# 08_ETHERNET.net
KiCad netlist of a schematic drawn in Altium Designer
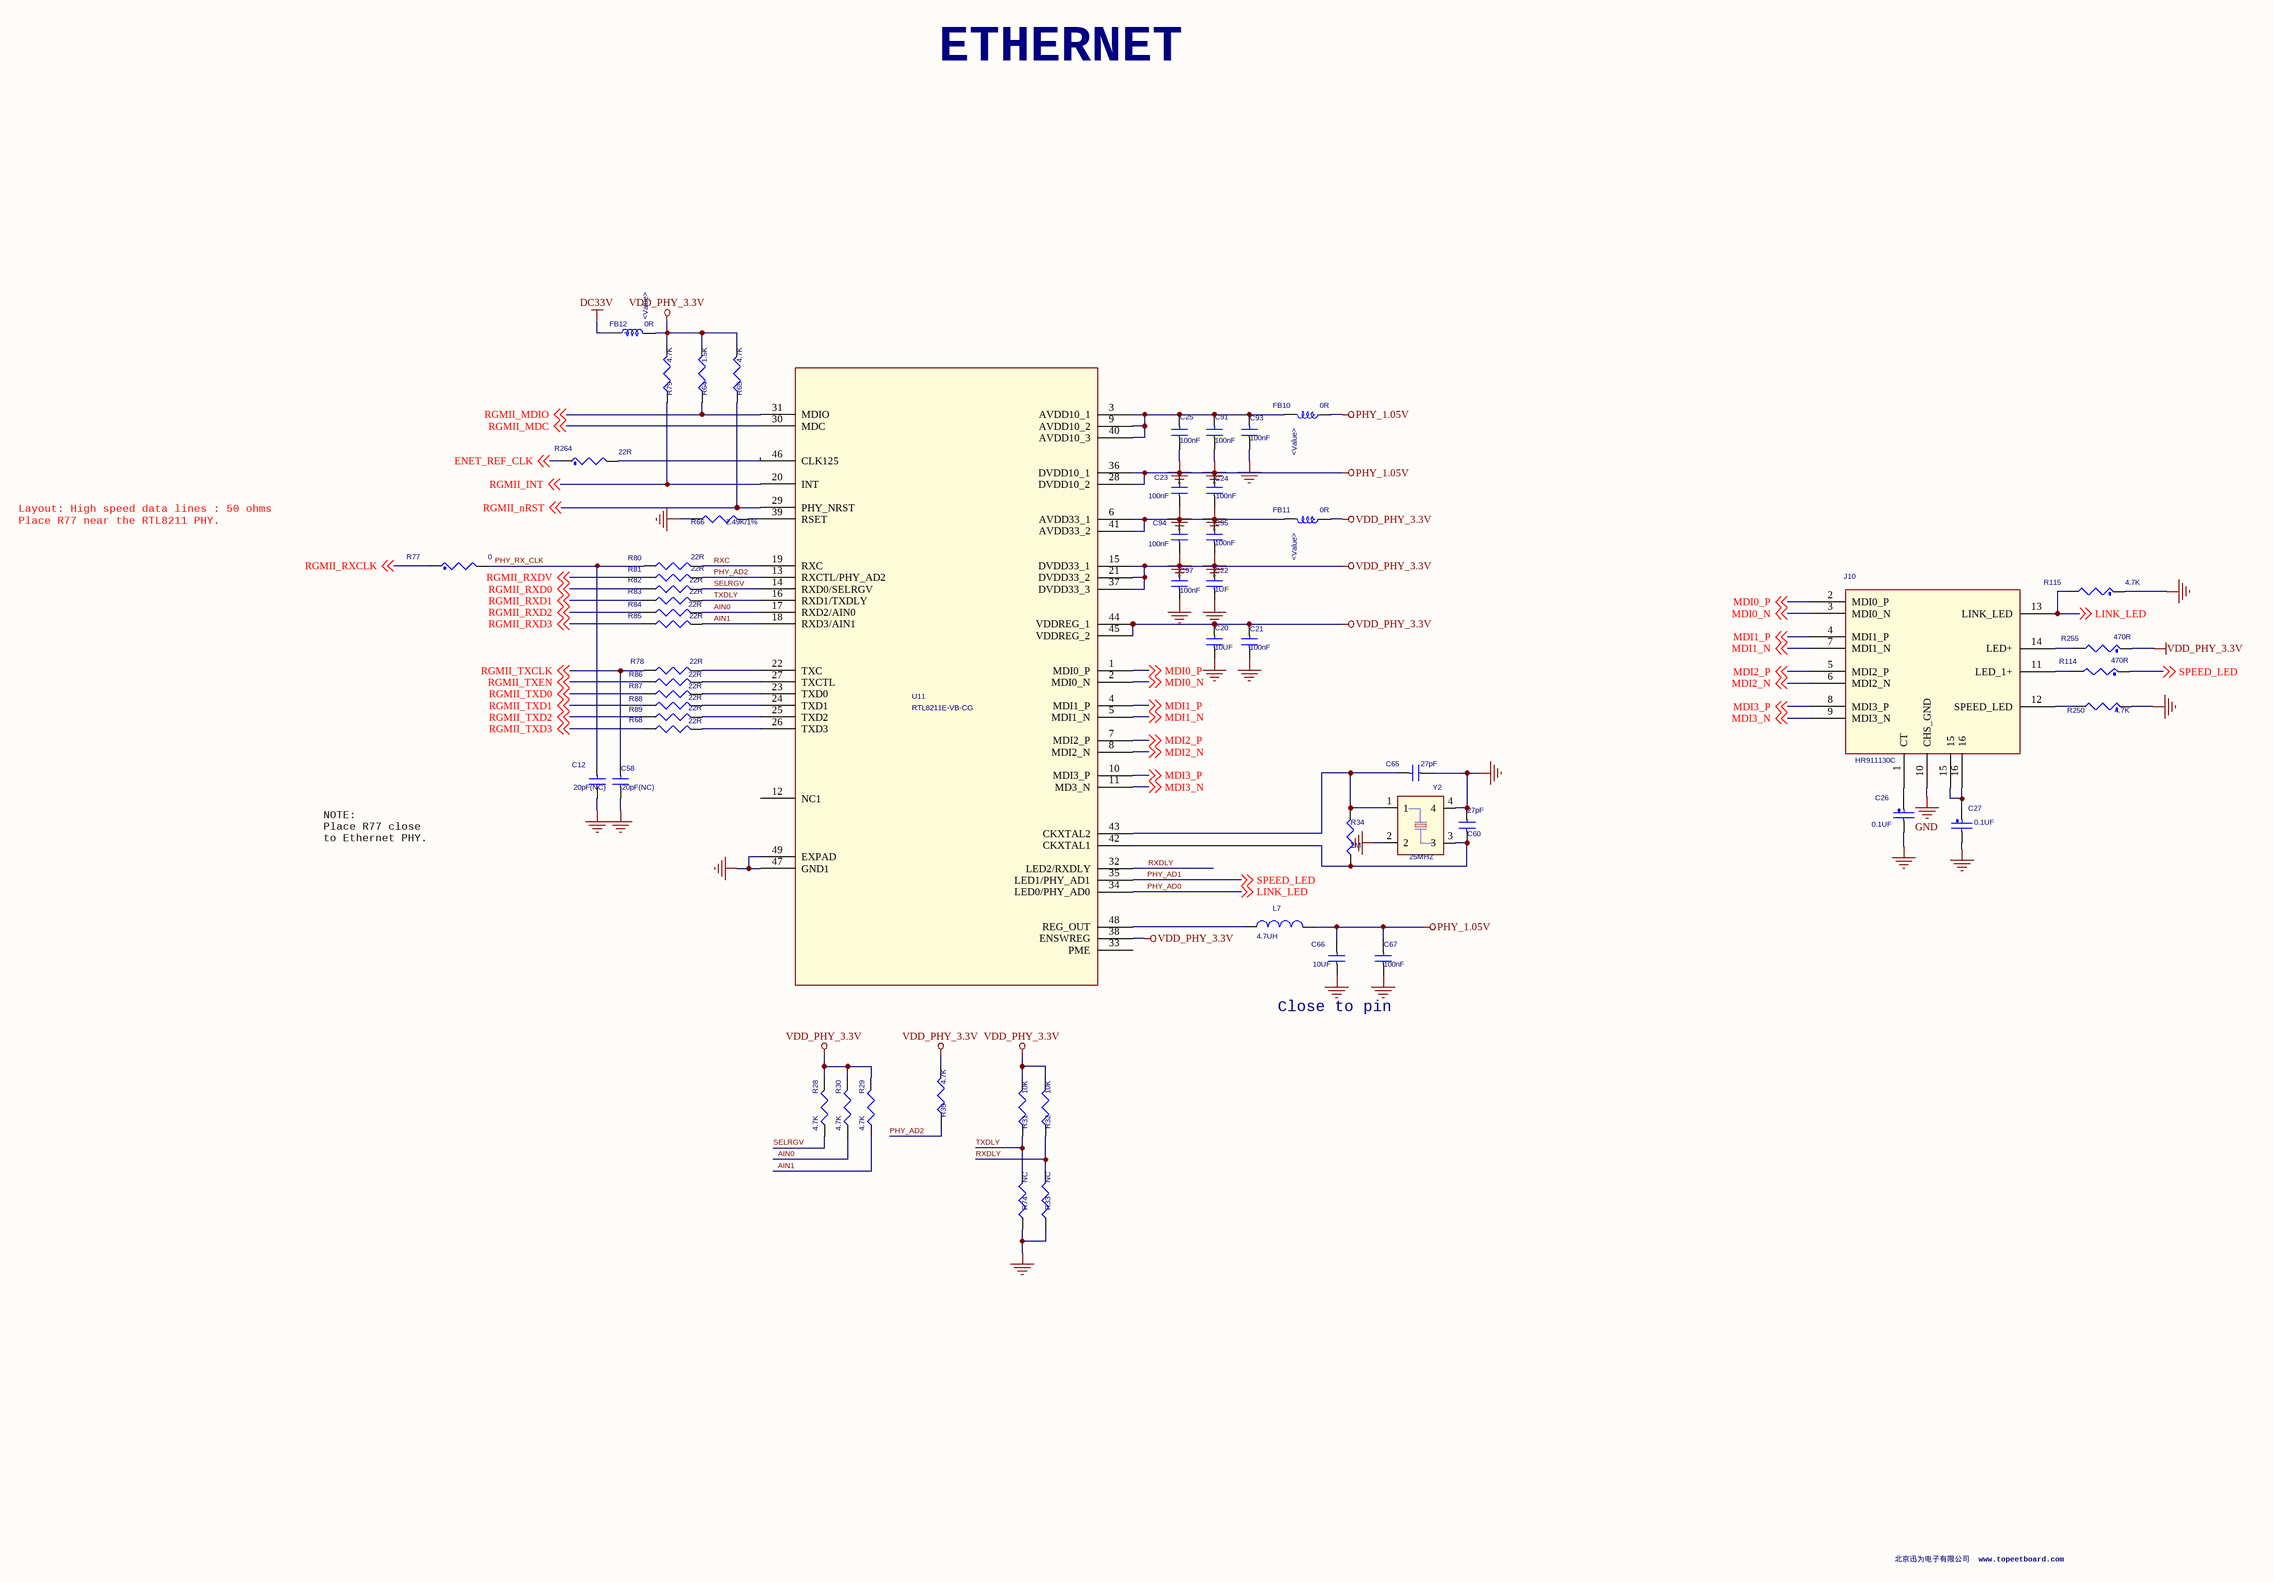
[diagram p0: 08 ETHERNET.SchDoc]

(export (version "E")
  (design (tool "Eeschema 10.0.6"))
  (components
    (comp (ref "C12") (value "20pF(NC)") (libsource (lib "*") (part "CAP")))
    (comp (ref "C20") (value "10UF") (libsource (lib "*") (part "CAP")))
    (comp (ref "C21") (value "100nF") (libsource (lib "*") (part "CAP")))
    (comp (ref "C22") (value "1UF") (libsource (lib "*") (part "CAP")))
    (comp (ref "C23") (value "100nF") (libsource (lib "*") (part "CAP")))
    (comp (ref "C24") (value "100nF") (libsource (lib "*") (part "CAP")))
    (comp (ref "C25") (value "100nF") (libsource (lib "*") (part "CAP")))
    (comp (ref "C26")
      (value "0.1UF")
      (description "CAP CER 0.1UF 16V 10% X7R 0402")
      (fields (field (name "TOLERANCE") "10%") (field (name "VOLTAGE") "16V"))
      (libsource (lib "*") (part "CAP_NP"))
    )
    (comp (ref "C27")
      (value "0.1UF")
      (description "CAP CER 0.1UF 16V 10% X7R 0402")
      (fields (field (name "VOLTAGE") "16V") (field (name "TOLERANCE") "10%"))
      (libsource (lib "*") (part "CAP_NP"))
    )
    (comp (ref "C58") (value "20pF(NC)") (libsource (lib "*") (part "CAP")))
    (comp (ref "C60") (value "27pF") (libsource (lib "*") (part "CAP")))
    (comp (ref "C65") (value "27pF") (libsource (lib "*") (part "CAP")))
    (comp (ref "C66") (value "10UF") (libsource (lib "*") (part "CAP")))
    (comp (ref "C67") (value "100nF") (libsource (lib "*") (part "CAP")))
    (comp (ref "C91") (value "100nF") (libsource (lib "*") (part "CAP")))
    (comp (ref "C93") (value "100nF") (libsource (lib "*") (part "CAP")))
    (comp (ref "C94") (value "100nF") (libsource (lib "*") (part "CAP")))
    (comp (ref "C95") (value "100nF") (libsource (lib "*") (part "CAP")))
    (comp (ref "C97") (value "100nF") (libsource (lib "*") (part "CAP")))
    (comp (ref "FB10")
      (value "0R")
      (footprint "L0603")
      (description "Inductor,0402，10ohm@100M,")
      (fields
        (field (name "5TH PART FIELD") "<Value>")
        (field (name "MANUFACTURER PART NUMBER") "BLM15AG100SN1")
        (field (name "MANUFACTURER") "Murata")
      )
      (libsource (lib "*") (part "IND_EMI"))
    )
    (comp (ref "FB11")
      (value "0R")
      (footprint "L0603")
      (description "Inductor,0402，10ohm@100M,")
      (fields
        (field (name "5TH PART FIELD") "<Value>")
        (field (name "MANUFACTURER PART NUMBER") "BLM15AG100SN1")
        (field (name "MANUFACTURER") "Murata")
      )
      (libsource (lib "*") (part "IND_EMI"))
    )
    (comp (ref "FB12")
      (value "0R")
      (footprint "L0603")
      (description "Inductor,0402，10ohm@100M,")
      (fields
        (field (name "5TH PART FIELD") "<Value>")
        (field (name "MANUFACTURER PART NUMBER") "BLM15AG100SN1")
        (field (name "MANUFACTURER") "Murata")
      )
      (libsource (lib "*") (part "IND_EMI"))
    )
    (comp (ref "J10") (value "HR911130C") (libsource (lib "*") (part "HR911130C_0")))
    (comp (ref "L7") (value "4.7UH") (libsource (lib "*") (part "INDUCTOR")))
    (comp (ref "R28") (value "4.7K") (libsource (lib "*") (part "RES")))
    (comp (ref "R29") (value "4.7K") (libsource (lib "*") (part "RES")))
    (comp (ref "R30") (value "4.7K") (libsource (lib "*") (part "RES")))
    (comp (ref "R31") (value "10K") (libsource (lib "*") (part "RES")))
    (comp (ref "R32") (value "10K") (libsource (lib "*") (part "RES")))
    (comp (ref "R33") (value "NC") (libsource (lib "*") (part "RES")))
    (comp (ref "R34") (value "1M") (libsource (lib "*") (part "RES")))
    (comp (ref "R35") (value "4.7K") (libsource (lib "*") (part "RES")))
    (comp (ref "R64") (value "1.5K") (libsource (lib "*") (part "RES")))
    (comp (ref "R65") (value "4.7K") (libsource (lib "*") (part "RES")))
    (comp (ref "R66") (value "2.49K/1%") (libsource (lib "*") (part "RES")))
    (comp (ref "R68") (value "22R") (libsource (lib "*") (part "RES")))
    (comp (ref "R74") (value "NC") (libsource (lib "*") (part "RES")))
    (comp (ref "R77")
      (value "0")
      (description "RES MF ZERO OHM 1/10W -- 0402")
      (libsource (lib "*") (part "RES_Dup1"))
    )
    (comp (ref "R78") (value "22R") (libsource (lib "*") (part "RES")))
    (comp (ref "R79") (value "4.7K") (libsource (lib "*") (part "RES")))
    (comp (ref "R80") (value "22R") (libsource (lib "*") (part "RES")))
    (comp (ref "R81") (value "22R") (libsource (lib "*") (part "RES")))
    (comp (ref "R82") (value "22R") (libsource (lib "*") (part "RES")))
    (comp (ref "R83") (value "22R") (libsource (lib "*") (part "RES")))
    (comp (ref "R84") (value "22R") (libsource (lib "*") (part "RES")))
    (comp (ref "R85") (value "22R") (libsource (lib "*") (part "RES")))
    (comp (ref "R86") (value "22R") (libsource (lib "*") (part "RES")))
    (comp (ref "R87") (value "22R") (libsource (lib "*") (part "RES")))
    (comp (ref "R88") (value "22R") (libsource (lib "*") (part "RES")))
    (comp (ref "R89") (value "22R") (libsource (lib "*") (part "RES")))
    (comp (ref "R114")
      (value "470R")
      (description "RES MF 270 OHM 1/16W 5% 0402")
      (fields (field (name "TOLERANCE") "5%"))
      (libsource (lib "*") (part "RES_Dup1"))
    )
    (comp (ref "R115")
      (value "4.7K")
      (description "RES MF 270 OHM 1/16W 5% 0402")
      (fields (field (name "TOLERANCE") "5%"))
      (libsource (lib "*") (part "RES_Dup1"))
    )
    (comp (ref "R250")
      (value "4.7K")
      (description "RES MF 270 OHM 1/16W 5% 0402")
      (fields (field (name "TOLERANCE") "5%"))
      (libsource (lib "*") (part "RES_Dup1"))
    )
    (comp (ref "R255")
      (value "470R")
      (description "RES MF 270 OHM 1/16W 5% 0402")
      (fields (field (name "TOLERANCE") "5%"))
      (libsource (lib "*") (part "RES_Dup1"))
    )
    (comp (ref "R264")
      (value "22R")
      (description "RES MF ZERO OHM 1/10W -- 0402")
      (libsource (lib "*") (part "RES_Dup1"))
    )
    (comp (ref "U11") (value "RTL8211E-VB-CG") (libsource (lib "*") (part "RTL8211E-VB-GC")))
    (comp (ref "Y2") (value "25MHZ") (libsource (lib "*") (part "Crystal-SMD4P")))
  )
  (nets
    (net (code "1") (name "/AIN0") (class "Default")
      (node (ref "R30") (pin "1") (pinfunction "1_1") (pintype "passive"))
      (node (ref "R84") (pin "2") (pinfunction "2_2") (pintype "passive"))
      (node (ref "U11") (pin "17") (pinfunction "RXD2/AIN0_17") (pintype "passive"))
    )
    (net (code "2") (name "/AIN1") (class "Default")
      (node (ref "R29") (pin "1") (pinfunction "1_1") (pintype "passive"))
      (node (ref "R85") (pin "2") (pinfunction "2_2") (pintype "passive"))
      (node (ref "U11") (pin "18") (pinfunction "RXD3/AIN1_18") (pintype "passive"))
    )
    (net (code "3") (name "/PHY_AD2") (class "Default")
      (node (ref "R35") (pin "1") (pinfunction "1_1") (pintype "passive"))
      (node (ref "R81") (pin "2") (pinfunction "2_2") (pintype "passive"))
      (node (ref "U11") (pin "13") (pinfunction "RXCTL/PHY_AD2_13") (pintype "passive"))
    )
    (net (code "4") (name "/PHY_RX_CLK") (class "Default")
      (node (ref "C12") (pin "2") (pinfunction "2_2") (pintype "passive"))
      (node (ref "R77") (pin "2") (pinfunction "2_2") (pintype "passive"))
      (node (ref "R80") (pin "1") (pinfunction "1_1") (pintype "passive"))
    )
    (net (code "5") (name "/RXC") (class "Default")
      (node (ref "R80") (pin "2") (pinfunction "2_2") (pintype "passive"))
      (node (ref "U11") (pin "19") (pinfunction "RXC_19") (pintype "passive"))
    )
    (net (code "6") (name "/RXDLY") (class "Default")
      (node (ref "R32") (pin "1") (pinfunction "1_1") (pintype "passive"))
      (node (ref "R33") (pin "2") (pinfunction "2_2") (pintype "passive"))
      (node (ref "U11") (pin "32") (pinfunction "LED2/RXDLY_32") (pintype "passive"))
    )
    (net (code "7") (name "/SELRGV") (class "Default")
      (node (ref "R28") (pin "1") (pinfunction "1_1") (pintype "passive"))
      (node (ref "R82") (pin "2") (pinfunction "2_2") (pintype "passive"))
      (node (ref "U11") (pin "14") (pinfunction "RXD0/SELRGV_14") (pintype "passive"))
    )
    (net (code "8") (name "/TXDLY") (class "Default")
      (node (ref "R31") (pin "1") (pinfunction "1_1") (pintype "passive"))
      (node (ref "R74") (pin "2") (pinfunction "2_2") (pintype "passive"))
      (node (ref "R83") (pin "2") (pinfunction "2_2") (pintype "passive"))
      (node (ref "U11") (pin "16") (pinfunction "RXD1/TXDLY_16") (pintype "passive"))
    )
    (net (code "9") (name "DC33V") (class "Default")
      (node (ref "FB12") (pin "1") (pinfunction "1_1") (pintype "passive"))
    )
    (net (code "10") (name "ENET_REF_CLK") (class "Default")
      (node (ref "R264") (pin "1") (pinfunction "1_1") (pintype "passive"))
    )
    (net (code "11") (name "GND") (class "Default")
      (node (ref "C12") (pin "1") (pinfunction "1_1") (pintype "passive"))
      (node (ref "C20") (pin "1") (pinfunction "1_1") (pintype "passive"))
      (node (ref "C21") (pin "1") (pinfunction "1_1") (pintype "passive"))
      (node (ref "C22") (pin "1") (pinfunction "1_1") (pintype "passive"))
      (node (ref "C23") (pin "1") (pinfunction "1_1") (pintype "passive"))
      (node (ref "C24") (pin "1") (pinfunction "1_1") (pintype "passive"))
      (node (ref "C25") (pin "1") (pinfunction "1_1") (pintype "passive"))
      (node (ref "C26") (pin "2") (pinfunction "2_2") (pintype "passive"))
      (node (ref "C27") (pin "2") (pinfunction "2_2") (pintype "passive"))
      (node (ref "C58") (pin "1") (pinfunction "1_1") (pintype "passive"))
      (node (ref "C60") (pin "1") (pinfunction "1_1") (pintype "passive"))
      (node (ref "C65") (pin "1") (pinfunction "1_1") (pintype "passive"))
      (node (ref "C66") (pin "1") (pinfunction "1_1") (pintype "passive"))
      (node (ref "C67") (pin "1") (pinfunction "1_1") (pintype "passive"))
      (node (ref "C91") (pin "1") (pinfunction "1_1") (pintype "passive"))
      (node (ref "C93") (pin "1") (pinfunction "1_1") (pintype "passive"))
      (node (ref "C94") (pin "1") (pinfunction "1_1") (pintype "passive"))
      (node (ref "C95") (pin "1") (pinfunction "1_1") (pintype "passive"))
      (node (ref "C97") (pin "1") (pinfunction "1_1") (pintype "passive"))
      (node (ref "J10") (pin "10") (pinfunction "CHS_GND_10") (pintype "passive"))
      (node (ref "R115") (pin "1") (pinfunction "1_1") (pintype "passive"))
      (node (ref "R250") (pin "1") (pinfunction "1_1") (pintype "passive"))
      (node (ref "R33") (pin "1") (pinfunction "1_1") (pintype "passive"))
      (node (ref "R66") (pin "1") (pinfunction "1_1") (pintype "passive"))
      (node (ref "R74") (pin "1") (pinfunction "1_1") (pintype "passive"))
      (node (ref "U11") (pin "47") (pinfunction "GND1_47") (pintype "passive"))
      (node (ref "U11") (pin "49") (pinfunction "EXPAD_49") (pintype "passive"))
      (node (ref "Y2") (pin "2") (pinfunction "2_2") (pintype "passive"))
      (node (ref "Y2") (pin "4") (pinfunction "4_4") (pintype "passive"))
    )
    (net (code "12") (name "LINK_LED") (class "Default")
      (node (ref "J10") (pin "13") (pinfunction "LINK_LED_13") (pintype "passive"))
      (node (ref "R115") (pin "2") (pinfunction "2_2") (pintype "passive"))
      (node (ref "U11") (pin "34") (pinfunction "LED0/PHY_AD0_34") (pintype "passive"))
    )
    (net (code "13") (name "MDI0_N") (class "Default")
      (node (ref "J10") (pin "3") (pinfunction "MDI0_N_3") (pintype "passive"))
      (node (ref "U11") (pin "2") (pinfunction "MDI0_N_2") (pintype "passive"))
    )
    (net (code "14") (name "MDI0_P") (class "Default")
      (node (ref "J10") (pin "2") (pinfunction "MDI0_P_2") (pintype "passive"))
      (node (ref "U11") (pin "1") (pinfunction "MDI0_P_1") (pintype "passive"))
    )
    (net (code "15") (name "MDI1_N") (class "Default")
      (node (ref "J10") (pin "7") (pinfunction "MDI1_N_7") (pintype "passive"))
      (node (ref "U11") (pin "5") (pinfunction "MDI1_N_5") (pintype "passive"))
    )
    (net (code "16") (name "MDI1_P") (class "Default")
      (node (ref "J10") (pin "4") (pinfunction "MDI1_P_4") (pintype "passive"))
      (node (ref "U11") (pin "4") (pinfunction "MDI1_P_4") (pintype "passive"))
    )
    (net (code "17") (name "MDI2_N") (class "Default")
      (node (ref "J10") (pin "6") (pinfunction "MDI2_N_6") (pintype "passive"))
      (node (ref "U11") (pin "8") (pinfunction "MDI2_N_8") (pintype "passive"))
    )
    (net (code "18") (name "MDI2_P") (class "Default")
      (node (ref "J10") (pin "5") (pinfunction "MDI2_P_5") (pintype "passive"))
      (node (ref "U11") (pin "7") (pinfunction "MDI2_P_7") (pintype "passive"))
    )
    (net (code "19") (name "MDI3_N") (class "Default")
      (node (ref "J10") (pin "9") (pinfunction "MDI3_N_9") (pintype "passive"))
      (node (ref "U11") (pin "11") (pinfunction "MD3_N_11") (pintype "passive"))
    )
    (net (code "20") (name "MDI3_P") (class "Default")
      (node (ref "J10") (pin "8") (pinfunction "MDI3_P_8") (pintype "passive"))
      (node (ref "U11") (pin "10") (pinfunction "MDI3_P_10") (pintype "passive"))
    )
    (net (code "21") (name "Net-(C27-Pad1)") (class "Default")
      (node (ref "C27") (pin "1") (pinfunction "1_1") (pintype "passive"))
      (node (ref "J10") (pin "15") (pinfunction "15_15") (pintype "passive"))
      (node (ref "J10") (pin "16") (pinfunction "16_16") (pintype "passive"))
    )
    (net (code "22") (name "Net-(J10-CT)") (class "Default")
      (node (ref "C26") (pin "1") (pinfunction "1_1") (pintype "passive"))
      (node (ref "J10") (pin "1") (pinfunction "CT_1") (pintype "passive"))
    )
    (net (code "23") (name "Net-(J10-LED+)") (class "Default")
      (node (ref "J10") (pin "14") (pinfunction "LED+_14") (pintype "passive"))
      (node (ref "R255") (pin "2") (pinfunction "2_2") (pintype "passive"))
    )
    (net (code "24") (name "Net-(J10-LED_1+)") (class "Default")
      (node (ref "J10") (pin "11") (pinfunction "LED_1+_11") (pintype "passive"))
      (node (ref "R114") (pin "2") (pinfunction "2_2") (pintype "passive"))
    )
    (net (code "25") (name "Net-(J10-SPEED_LED)") (class "Default")
      (node (ref "J10") (pin "12") (pinfunction "SPEED_LED_12") (pintype "passive"))
      (node (ref "R250") (pin "2") (pinfunction "2_2") (pintype "passive"))
    )
    (net (code "26") (name "Net-(U11-AVDD10_1)") (class "Default")
      (node (ref "C25") (pin "2") (pinfunction "2_2") (pintype "passive"))
      (node (ref "C91") (pin "2") (pinfunction "2_2") (pintype "passive"))
      (node (ref "C93") (pin "2") (pinfunction "2_2") (pintype "passive"))
      (node (ref "FB10") (pin "2") (pinfunction "2_2") (pintype "passive"))
      (node (ref "U11") (pin "3") (pinfunction "AVDD10_1_3") (pintype "passive"))
      (node (ref "U11") (pin "40") (pinfunction "AVDD10_3_40") (pintype "passive"))
      (node (ref "U11") (pin "9") (pinfunction "AVDD10_2_9") (pintype "passive"))
    )
    (net (code "27") (name "Net-(U11-AVDD33_1)") (class "Default")
      (node (ref "C94") (pin "2") (pinfunction "2_2") (pintype "passive"))
      (node (ref "C95") (pin "2") (pinfunction "2_2") (pintype "passive"))
      (node (ref "FB11") (pin "2") (pinfunction "2_2") (pintype "passive"))
      (node (ref "U11") (pin "41") (pinfunction "AVDD33_2_41") (pintype "passive"))
      (node (ref "U11") (pin "6") (pinfunction "AVDD33_1_6") (pintype "passive"))
    )
    (net (code "28") (name "Net-(U11-CKXTAL1)") (class "Default")
      (node (ref "C60") (pin "2") (pinfunction "2_2") (pintype "passive"))
      (node (ref "R34") (pin "1") (pinfunction "1_1") (pintype "passive"))
      (node (ref "U11") (pin "42") (pinfunction "CKXTAL1_42") (pintype "passive"))
      (node (ref "Y2") (pin "3") (pinfunction "3_3") (pintype "passive"))
    )
    (net (code "29") (name "Net-(U11-CKXTAL2)") (class "Default")
      (node (ref "C65") (pin "2") (pinfunction "2_2") (pintype "passive"))
      (node (ref "R34") (pin "2") (pinfunction "2_2") (pintype "passive"))
      (node (ref "U11") (pin "43") (pinfunction "CKXTAL2_43") (pintype "passive"))
      (node (ref "Y2") (pin "1") (pinfunction "1_1") (pintype "passive"))
    )
    (net (code "30") (name "Net-(U11-CLK125)") (class "Default")
      (node (ref "R264") (pin "2") (pinfunction "2_2") (pintype "passive"))
      (node (ref "U11") (pin "46") (pinfunction "CLK125_46") (pintype "passive"))
    )
    (net (code "31") (name "Net-(U11-REG_OUT)") (class "Default")
      (node (ref "L7") (pin "1") (pinfunction "1_1") (pintype "passive"))
      (node (ref "U11") (pin "48") (pinfunction "REG_OUT_48") (pintype "passive"))
    )
    (net (code "32") (name "Net-(U11-RSET)") (class "Default")
      (node (ref "R66") (pin "2") (pinfunction "2_2") (pintype "passive"))
      (node (ref "U11") (pin "39") (pinfunction "RSET_39") (pintype "passive"))
    )
    (net (code "33") (name "Net-(U11-TXC)") (class "Default")
      (node (ref "R78") (pin "2") (pinfunction "2_2") (pintype "passive"))
      (node (ref "U11") (pin "22") (pinfunction "TXC_22") (pintype "passive"))
    )
    (net (code "34") (name "Net-(U11-TXCTL)") (class "Default")
      (node (ref "R86") (pin "2") (pinfunction "2_2") (pintype "passive"))
      (node (ref "U11") (pin "27") (pinfunction "TXCTL_27") (pintype "passive"))
    )
    (net (code "35") (name "Net-(U11-TXD0)") (class "Default")
      (node (ref "R87") (pin "2") (pinfunction "2_2") (pintype "passive"))
      (node (ref "U11") (pin "23") (pinfunction "TXD0_23") (pintype "passive"))
    )
    (net (code "36") (name "Net-(U11-TXD1)") (class "Default")
      (node (ref "R88") (pin "2") (pinfunction "2_2") (pintype "passive"))
      (node (ref "U11") (pin "24") (pinfunction "TXD1_24") (pintype "passive"))
    )
    (net (code "37") (name "Net-(U11-TXD2)") (class "Default")
      (node (ref "R89") (pin "2") (pinfunction "2_2") (pintype "passive"))
      (node (ref "U11") (pin "25") (pinfunction "TXD2_25") (pintype "passive"))
    )
    (net (code "38") (name "Net-(U11-TXD3)") (class "Default")
      (node (ref "R68") (pin "2") (pinfunction "2_2") (pintype "passive"))
      (node (ref "U11") (pin "26") (pinfunction "TXD3_26") (pintype "passive"))
    )
    (net (code "39") (name "PHY_1.05V") (class "Default")
      (node (ref "C23") (pin "2") (pinfunction "2_2") (pintype "passive"))
      (node (ref "C24") (pin "2") (pinfunction "2_2") (pintype "passive"))
      (node (ref "C66") (pin "2") (pinfunction "2_2") (pintype "passive"))
      (node (ref "C67") (pin "2") (pinfunction "2_2") (pintype "passive"))
      (node (ref "FB10") (pin "1") (pinfunction "1_1") (pintype "passive"))
      (node (ref "L7") (pin "2") (pinfunction "2_2") (pintype "passive"))
      (node (ref "U11") (pin "28") (pinfunction "DVDD10_2_28") (pintype "passive"))
      (node (ref "U11") (pin "36") (pinfunction "DVDD10_1_36") (pintype "passive"))
    )
    (net (code "40") (name "RGMII_INT") (class "Default")
      (node (ref "R79") (pin "1") (pinfunction "1_1") (pintype "passive"))
      (node (ref "U11") (pin "20") (pinfunction "INT_20") (pintype "passive"))
    )
    (net (code "41") (name "RGMII_MDC") (class "Default")
      (node (ref "U11") (pin "30") (pinfunction "MDC_30") (pintype "passive"))
    )
    (net (code "42") (name "RGMII_MDIO") (class "Default")
      (node (ref "R64") (pin "1") (pinfunction "1_1") (pintype "passive"))
      (node (ref "U11") (pin "31") (pinfunction "MDIO_31") (pintype "passive"))
    )
    (net (code "43") (name "RGMII_RXCLK") (class "Default")
      (node (ref "R77") (pin "1") (pinfunction "1_1") (pintype "passive"))
    )
    (net (code "44") (name "RGMII_RXD0") (class "Default")
      (node (ref "R82") (pin "1") (pinfunction "1_1") (pintype "passive"))
    )
    (net (code "45") (name "RGMII_RXD1") (class "Default")
      (node (ref "R83") (pin "1") (pinfunction "1_1") (pintype "passive"))
    )
    (net (code "46") (name "RGMII_RXD2") (class "Default")
      (node (ref "R84") (pin "1") (pinfunction "1_1") (pintype "passive"))
    )
    (net (code "47") (name "RGMII_RXD3") (class "Default")
      (node (ref "R85") (pin "1") (pinfunction "1_1") (pintype "passive"))
    )
    (net (code "48") (name "RGMII_RXDV") (class "Default")
      (node (ref "R81") (pin "1") (pinfunction "1_1") (pintype "passive"))
    )
    (net (code "49") (name "RGMII_TXCLK") (class "Default")
      (node (ref "C58") (pin "2") (pinfunction "2_2") (pintype "passive"))
      (node (ref "R78") (pin "1") (pinfunction "1_1") (pintype "passive"))
    )
    (net (code "50") (name "RGMII_TXD0") (class "Default")
      (node (ref "R87") (pin "1") (pinfunction "1_1") (pintype "passive"))
    )
    (net (code "51") (name "RGMII_TXD1") (class "Default")
      (node (ref "R88") (pin "1") (pinfunction "1_1") (pintype "passive"))
    )
    (net (code "52") (name "RGMII_TXD2") (class "Default")
      (node (ref "R89") (pin "1") (pinfunction "1_1") (pintype "passive"))
    )
    (net (code "53") (name "RGMII_TXD3") (class "Default")
      (node (ref "R68") (pin "1") (pinfunction "1_1") (pintype "passive"))
    )
    (net (code "54") (name "RGMII_TXEN") (class "Default")
      (node (ref "R86") (pin "1") (pinfunction "1_1") (pintype "passive"))
    )
    (net (code "55") (name "RGMII_nRST") (class "Default")
      (node (ref "R65") (pin "1") (pinfunction "1_1") (pintype "passive"))
      (node (ref "U11") (pin "29") (pinfunction "PHY_NRST_29") (pintype "passive"))
    )
    (net (code "56") (name "SPEED_LED") (class "Default")
      (node (ref "R114") (pin "1") (pinfunction "1_1") (pintype "passive"))
      (node (ref "U11") (pin "35") (pinfunction "LED1/PHY_AD1_35") (pintype "passive"))
    )
    (net (code "57") (name "VDD_PHY_3.3V") (class "Default")
      (node (ref "C20") (pin "2") (pinfunction "2_2") (pintype "passive"))
      (node (ref "C21") (pin "2") (pinfunction "2_2") (pintype "passive"))
      (node (ref "C22") (pin "2") (pinfunction "2_2") (pintype "passive"))
      (node (ref "C97") (pin "2") (pinfunction "2_2") (pintype "passive"))
      (node (ref "FB11") (pin "1") (pinfunction "1_1") (pintype "passive"))
      (node (ref "FB12") (pin "2") (pinfunction "2_2") (pintype "passive"))
      (node (ref "R255") (pin "1") (pinfunction "1_1") (pintype "passive"))
      (node (ref "R28") (pin "2") (pinfunction "2_2") (pintype "passive"))
      (node (ref "R29") (pin "2") (pinfunction "2_2") (pintype "passive"))
      (node (ref "R30") (pin "2") (pinfunction "2_2") (pintype "passive"))
      (node (ref "R31") (pin "2") (pinfunction "2_2") (pintype "passive"))
      (node (ref "R32") (pin "2") (pinfunction "2_2") (pintype "passive"))
      (node (ref "R35") (pin "2") (pinfunction "2_2") (pintype "passive"))
      (node (ref "R64") (pin "2") (pinfunction "2_2") (pintype "passive"))
      (node (ref "R65") (pin "2") (pinfunction "2_2") (pintype "passive"))
      (node (ref "R79") (pin "2") (pinfunction "2_2") (pintype "passive"))
      (node (ref "U11") (pin "15") (pinfunction "DVDD33_1_15") (pintype "passive"))
      (node (ref "U11") (pin "21") (pinfunction "DVDD33_2_21") (pintype "passive"))
      (node (ref "U11") (pin "37") (pinfunction "DVDD33_3_37") (pintype "passive"))
      (node (ref "U11") (pin "38") (pinfunction "ENSWREG_38") (pintype "passive"))
      (node (ref "U11") (pin "44") (pinfunction "VDDREG_1_44") (pintype "passive"))
      (node (ref "U11") (pin "45") (pinfunction "VDDREG_2_45") (pintype "passive"))
    )
    (net (code "58") (name "unconnected-(U11-NC1-Pad12)") (class "Default")
      (node (ref "U11") (pin "12") (pinfunction "NC1_12") (pintype "passive"))
    )
    (net (code "59") (name "unconnected-(U11-PME-Pad33)") (class "Default")
      (node (ref "U11") (pin "33") (pinfunction "PME_33") (pintype "passive"))
    )
  )
)
